# NumberMaze.net
KiCad netlist of a schematic drawn in EAGLE
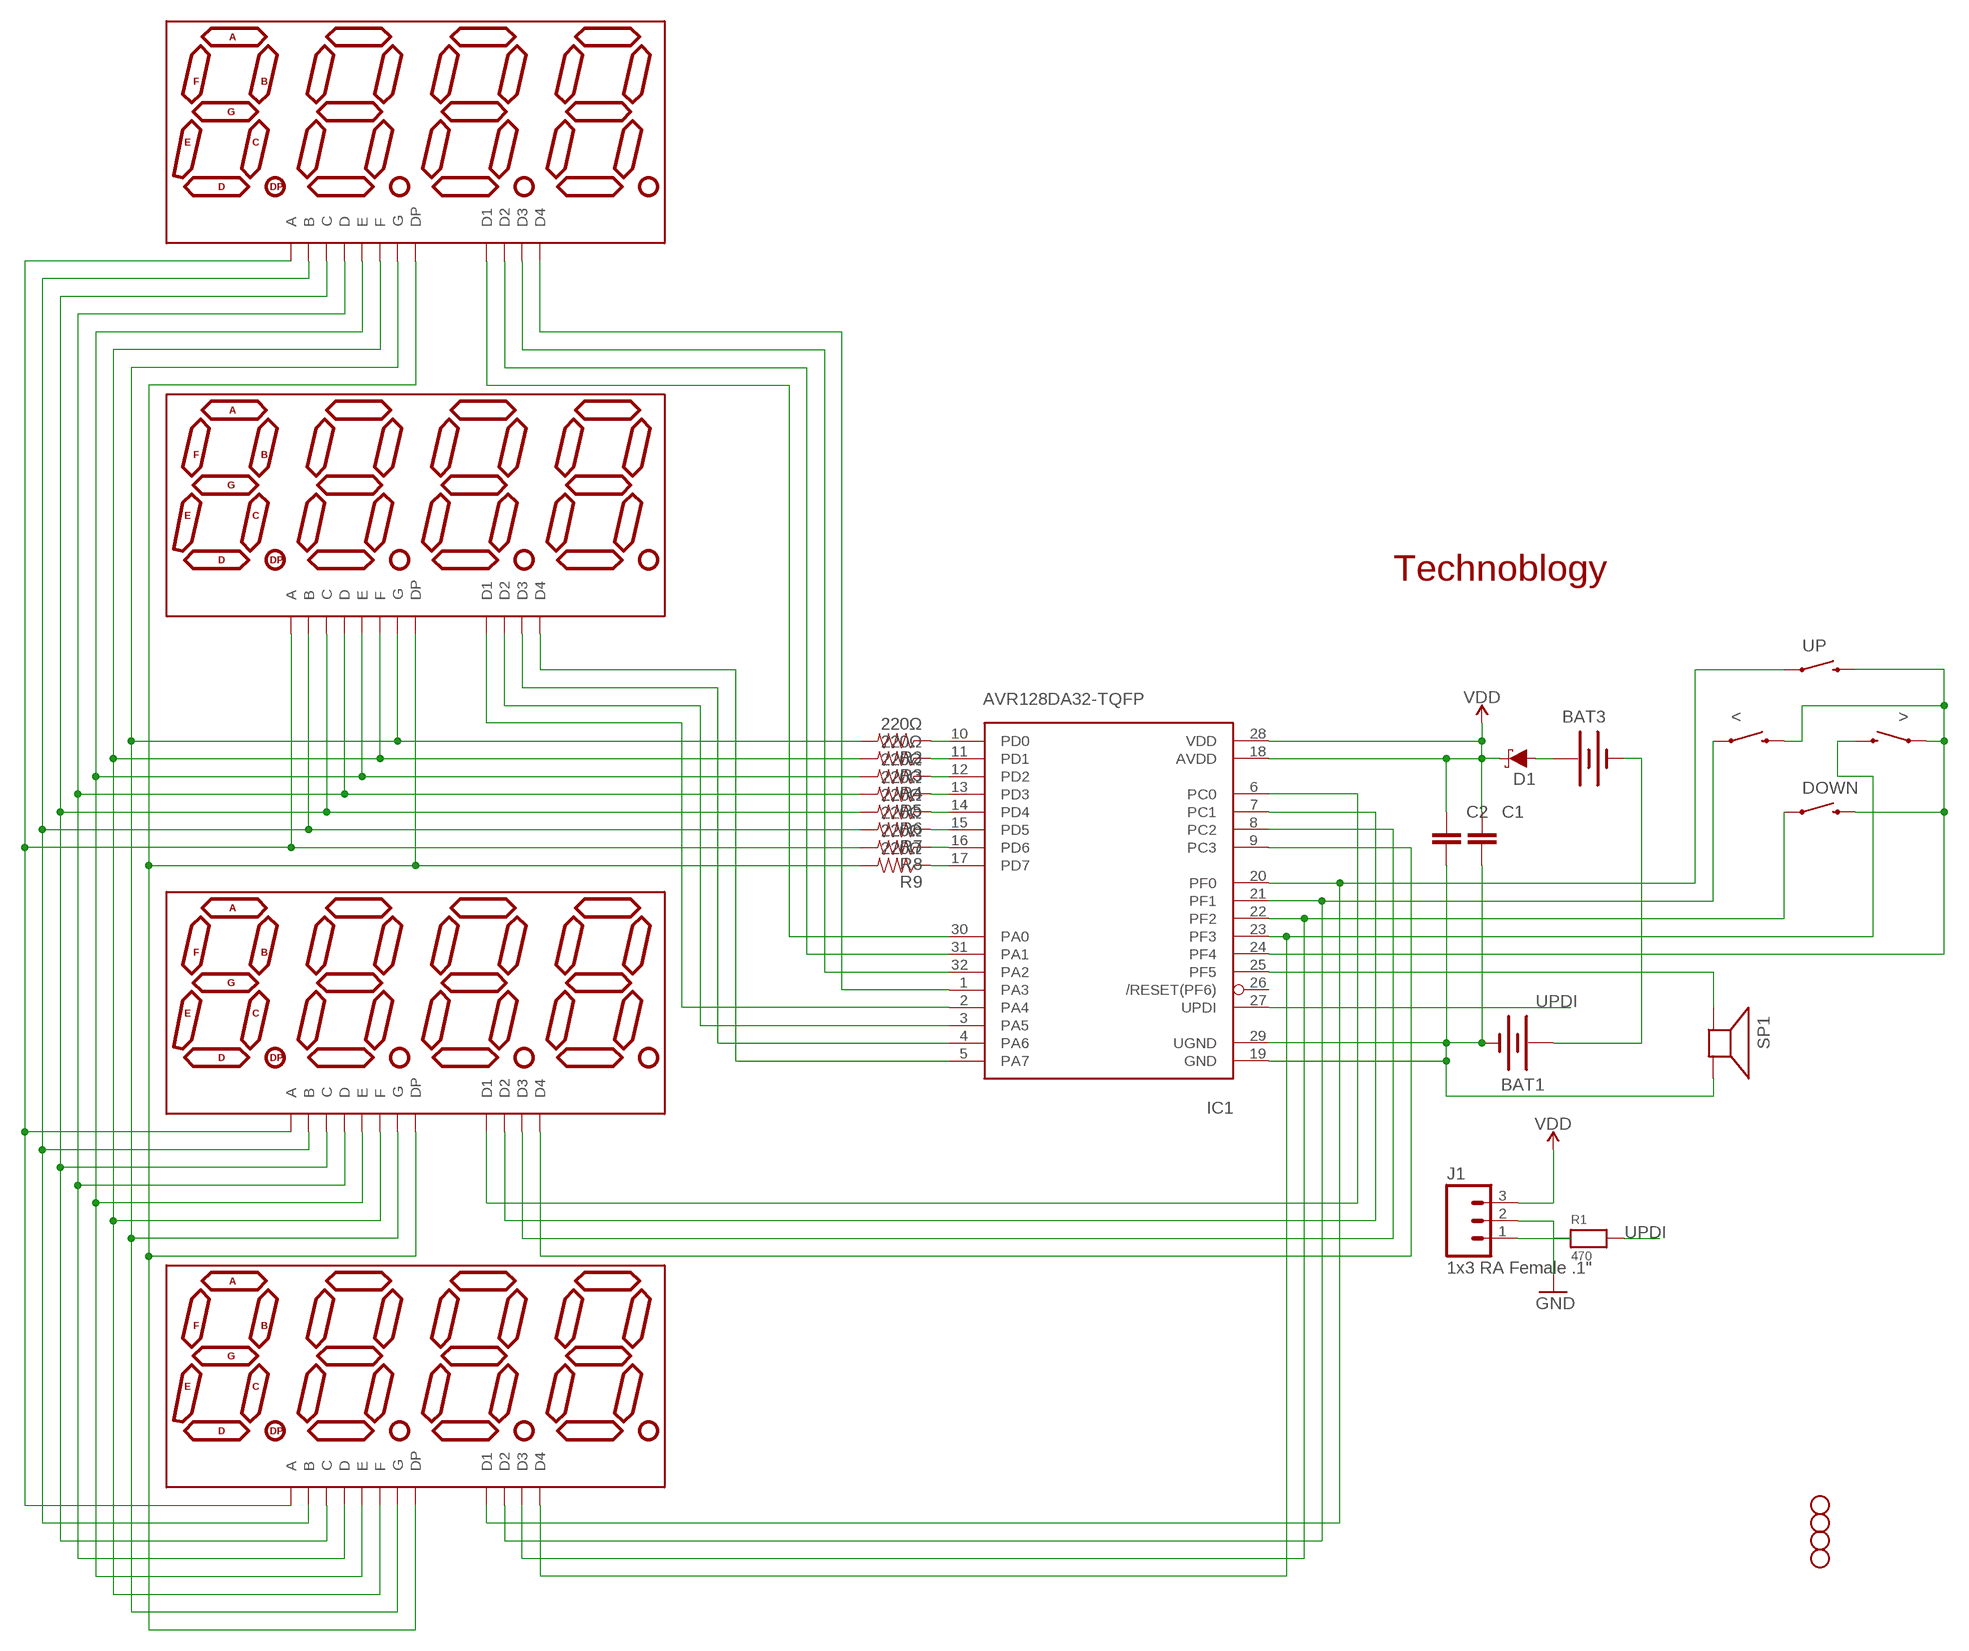
[diagram p0: schematic, sheet 1]

(export (version "E")
  (design (tool "Eeschema 10.0.6"))
  (components
    (comp (ref "<")
      (value "SWITCH-MOMENTARY-2PTH")
      (footprint "eagle-import:TACTILE-PTH")
      (libsource (lib "eagle-import") (part "SWITCH-MOMENTARY-2PTH"))
    )
    (comp (ref ">")
      (value "SWITCH-MOMENTARY-2PTH")
      (footprint "eagle-import:TACTILE-PTH")
      (libsource (lib "eagle-import") (part "SWITCH-MOMENTARY-2PTH"))
    )
    (comp (ref "BAT1")
      (value "BATTERYAA-KIT")
      (footprint "eagle-import:BATTERY-AA-KIT")
      (libsource (lib "eagle-import") (part "BATTERYAA-KIT"))
    )
    (comp (ref "BAT3")
      (value "BATTERYAA-KIT")
      (footprint "eagle-import:BATTERY-AA-KIT")
      (libsource (lib "eagle-import") (part "BATTERYAA-KIT"))
    )
    (comp (ref "C1")
      (value "100n")
      (footprint "eagle-import:0805")
      (libsource (lib "eagle-import") (part "CAP0805"))
    )
    (comp (ref "C2")
      (value "100n")
      (footprint "eagle-import:0805")
      (libsource (lib "eagle-import") (part "CAP0805"))
    )
    (comp (ref "D1")
      (value "3A/10V/280mV")
      (footprint "eagle-import:SOD-323")
      (libsource (lib "eagle-import") (part "DIODE-SCHOTTKY-BAT60A"))
    )
    (comp (ref "DISP1")
      (value "KYX-2381")
      (footprint "eagle-import:KYX-2381")
      (libsource (lib "eagle-import") (part "LD-2481-KYX-2381"))
    )
    (comp (ref "DISP2")
      (value "KYX-2381")
      (footprint "eagle-import:KYX-2381")
      (libsource (lib "eagle-import") (part "LD-2481-KYX-2381"))
    )
    (comp (ref "DISP3")
      (value "KYX-2381")
      (footprint "eagle-import:KYX-2381")
      (libsource (lib "eagle-import") (part "LD-2481-KYX-2381"))
    )
    (comp (ref "DISP4")
      (value "KYX-2381")
      (footprint "eagle-import:KYX-2381")
      (libsource (lib "eagle-import") (part "LD-2481-KYX-2381"))
    )
    (comp (ref "DOWN")
      (value "SWITCH-MOMENTARY-2PTH")
      (footprint "eagle-import:TACTILE-PTH")
      (libsource (lib "eagle-import") (part "SWITCH-MOMENTARY-2PTH"))
    )
    (comp (ref "IC1")
      (value "AVR128DA32-TQFP")
      (footprint "eagle-import:TQFP32-08")
      (libsource (lib "eagle-import") (part "AVR128DA32-TQFP"))
    )
    (comp (ref "J1")
      (value "1x3 RA Female .1\"")
      (footprint "eagle-import:1X03_SMD_RA_FEMALE")
      (libsource (lib "eagle-import") (part "M03SMD_RA_FEMALE"))
    )
    (comp (ref "JP1")
      (value "STAND-OFF")
      (footprint "eagle-import:STAND-OFF")
      (libsource (lib "eagle-import") (part "STAND-OFF"))
    )
    (comp (ref "JP2")
      (value "STAND-OFF")
      (footprint "eagle-import:STAND-OFF")
      (libsource (lib "eagle-import") (part "STAND-OFF"))
    )
    (comp (ref "JP4")
      (value "STAND-OFF")
      (footprint "eagle-import:STAND-OFF")
      (libsource (lib "eagle-import") (part "STAND-OFF"))
    )
    (comp (ref "JP5")
      (value "STAND-OFF")
      (footprint "eagle-import:STAND-OFF")
      (libsource (lib "eagle-import") (part "STAND-OFF"))
    )
    (comp (ref "R1")
      (value "470")
      (footprint "eagle-import:_0805MP")
      (libsource (lib "eagle-import") (part "RESISTOR_0805MP"))
    )
    (comp (ref "R2")
      (value "220Ω")
      (footprint "eagle-import:0805")
      (libsource (lib "eagle-import") (part "RESISTOR0805-RES"))
    )
    (comp (ref "R3")
      (value "220Ω")
      (footprint "eagle-import:0805")
      (libsource (lib "eagle-import") (part "RESISTOR0805-RES"))
    )
    (comp (ref "R4")
      (value "220Ω")
      (footprint "eagle-import:0805")
      (libsource (lib "eagle-import") (part "RESISTOR0805-RES"))
    )
    (comp (ref "R5")
      (value "220Ω")
      (footprint "eagle-import:0805")
      (libsource (lib "eagle-import") (part "RESISTOR0805-RES"))
    )
    (comp (ref "R6")
      (value "220Ω")
      (footprint "eagle-import:0805")
      (libsource (lib "eagle-import") (part "RESISTOR0805-RES"))
    )
    (comp (ref "R7")
      (value "220Ω")
      (footprint "eagle-import:0805")
      (libsource (lib "eagle-import") (part "RESISTOR0805-RES"))
    )
    (comp (ref "R8")
      (value "220Ω")
      (footprint "eagle-import:0805")
      (libsource (lib "eagle-import") (part "RESISTOR0805-RES"))
    )
    (comp (ref "R9")
      (value "220Ω")
      (footprint "eagle-import:0805")
      (libsource (lib "eagle-import") (part "RESISTOR0805-RES"))
    )
    (comp (ref "SP1")
      (value "SPEAKER/AL60P")
      (footprint "eagle-import:AL60P")
      (libsource (lib "eagle-import") (part "SPEAKER/AL60P"))
    )
    (comp (ref "UP")
      (value "SWITCH-MOMENTARY-2PTH")
      (footprint "eagle-import:TACTILE-PTH")
      (libsource (lib "eagle-import") (part "SWITCH-MOMENTARY-2PTH"))
    )
  )
  (nets
    (net (code "1") (name "/UPDI") (class "Default")
      (node (ref "IC1") (pin "27") (pinfunction "UPDI_27") (pintype "bidirectional"))
      (node (ref "R1") (pin "2") (pinfunction "2_2") (pintype "passive"))
    )
    (net (code "2") (name "GND") (class "Default")
      (node (ref "BAT1") (pin "GND@1") (pinfunction "-_GND@1") (pintype "power_in"))
      (node (ref "C1") (pin "2") (pinfunction "2_2") (pintype "passive"))
      (node (ref "C2") (pin "2") (pinfunction "2_2") (pintype "passive"))
      (node (ref "IC1") (pin "19") (pinfunction "GND_19") (pintype "bidirectional"))
      (node (ref "IC1") (pin "29") (pinfunction "UGND_29") (pintype "bidirectional"))
      (node (ref "J1") (pin "2") (pinfunction "2_2") (pintype "passive"))
      (node (ref "SP1") (pin "2") (pinfunction "-_2") (pintype "passive"))
    )
    (net (code "3") (name "Net-(<-2)") (class "Default")
      (node (ref "<") (pin "3") (pinfunction "2_3") (pintype "passive"))
      (node (ref ">") (pin "1") (pinfunction "1_1") (pintype "passive"))
      (node (ref "DOWN") (pin "3") (pinfunction "2_3") (pintype "passive"))
      (node (ref "IC1") (pin "24") (pinfunction "PF4_24") (pintype "bidirectional"))
      (node (ref "UP") (pin "3") (pinfunction "2_3") (pintype "passive"))
    )
    (net (code "4") (name "Net-(>-2)") (class "Default")
      (node (ref ">") (pin "3") (pinfunction "2_3") (pintype "passive"))
      (node (ref "DISP4") (pin "6") (pinfunction "D4_6") (pintype "bidirectional"))
      (node (ref "IC1") (pin "23") (pinfunction "PF3_23") (pintype "bidirectional"))
    )
    (net (code "5") (name "Net-(BAT1-+)") (class "Default")
      (node (ref "BAT1") (pin "PWR@1") (pinfunction "+_PWR@1") (pintype "power_in"))
      (node (ref "BAT3") (pin "GND@1") (pinfunction "-_GND@1") (pintype "power_in"))
    )
    (net (code "6") (name "Net-(BAT3-+)") (class "Default")
      (node (ref "BAT3") (pin "PWR@1") (pinfunction "+_PWR@1") (pintype "power_in"))
      (node (ref "D1") (pin "A") (pinfunction "A_A") (pintype "passive"))
    )
    (net (code "7") (name "Net-(DISP1-A)") (class "Default")
      (node (ref "DISP1") (pin "11") (pinfunction "A_11") (pintype "bidirectional"))
      (node (ref "DISP2") (pin "11") (pinfunction "A_11") (pintype "bidirectional"))
      (node (ref "DISP3") (pin "11") (pinfunction "A_11") (pintype "bidirectional"))
      (node (ref "DISP4") (pin "11") (pinfunction "A_11") (pintype "bidirectional"))
      (node (ref "R8") (pin "2") (pinfunction "2_2") (pintype "passive"))
    )
    (net (code "8") (name "Net-(DISP1-B)") (class "Default")
      (node (ref "DISP1") (pin "7") (pinfunction "B_7") (pintype "bidirectional"))
      (node (ref "DISP2") (pin "7") (pinfunction "B_7") (pintype "bidirectional"))
      (node (ref "DISP3") (pin "7") (pinfunction "B_7") (pintype "bidirectional"))
      (node (ref "DISP4") (pin "7") (pinfunction "B_7") (pintype "bidirectional"))
      (node (ref "R7") (pin "2") (pinfunction "2_2") (pintype "passive"))
    )
    (net (code "9") (name "Net-(DISP1-C)") (class "Default")
      (node (ref "DISP1") (pin "4") (pinfunction "C_4") (pintype "bidirectional"))
      (node (ref "DISP2") (pin "4") (pinfunction "C_4") (pintype "bidirectional"))
      (node (ref "DISP3") (pin "4") (pinfunction "C_4") (pintype "bidirectional"))
      (node (ref "DISP4") (pin "4") (pinfunction "C_4") (pintype "bidirectional"))
      (node (ref "R6") (pin "2") (pinfunction "2_2") (pintype "passive"))
    )
    (net (code "10") (name "Net-(DISP1-D)") (class "Default")
      (node (ref "DISP1") (pin "2") (pinfunction "D_2") (pintype "bidirectional"))
      (node (ref "DISP2") (pin "2") (pinfunction "D_2") (pintype "bidirectional"))
      (node (ref "DISP3") (pin "2") (pinfunction "D_2") (pintype "bidirectional"))
      (node (ref "DISP4") (pin "2") (pinfunction "D_2") (pintype "bidirectional"))
      (node (ref "R5") (pin "2") (pinfunction "2_2") (pintype "passive"))
    )
    (net (code "11") (name "Net-(DISP1-D1)") (class "Default")
      (node (ref "DISP1") (pin "12") (pinfunction "D1_12") (pintype "bidirectional"))
      (node (ref "IC1") (pin "30") (pinfunction "PA0_30") (pintype "bidirectional"))
    )
    (net (code "12") (name "Net-(DISP1-D2)") (class "Default")
      (node (ref "DISP1") (pin "9") (pinfunction "D2_9") (pintype "bidirectional"))
      (node (ref "IC1") (pin "31") (pinfunction "PA1_31") (pintype "bidirectional"))
    )
    (net (code "13") (name "Net-(DISP1-D3)") (class "Default")
      (node (ref "DISP1") (pin "8") (pinfunction "D3_8") (pintype "bidirectional"))
      (node (ref "IC1") (pin "32") (pinfunction "PA2_32") (pintype "bidirectional"))
    )
    (net (code "14") (name "Net-(DISP1-D4)") (class "Default")
      (node (ref "DISP1") (pin "6") (pinfunction "D4_6") (pintype "bidirectional"))
      (node (ref "IC1") (pin "1") (pinfunction "PA3_1") (pintype "bidirectional"))
    )
    (net (code "15") (name "Net-(DISP1-DP)") (class "Default")
      (node (ref "DISP1") (pin "3") (pinfunction "DP_3") (pintype "bidirectional"))
      (node (ref "DISP2") (pin "3") (pinfunction "DP_3") (pintype "bidirectional"))
      (node (ref "DISP3") (pin "3") (pinfunction "DP_3") (pintype "bidirectional"))
      (node (ref "DISP4") (pin "3") (pinfunction "DP_3") (pintype "bidirectional"))
      (node (ref "R9") (pin "2") (pinfunction "2_2") (pintype "passive"))
    )
    (net (code "16") (name "Net-(DISP1-E)") (class "Default")
      (node (ref "DISP1") (pin "1") (pinfunction "E_1") (pintype "bidirectional"))
      (node (ref "DISP2") (pin "1") (pinfunction "E_1") (pintype "bidirectional"))
      (node (ref "DISP3") (pin "1") (pinfunction "E_1") (pintype "bidirectional"))
      (node (ref "DISP4") (pin "1") (pinfunction "E_1") (pintype "bidirectional"))
      (node (ref "R4") (pin "2") (pinfunction "2_2") (pintype "passive"))
    )
    (net (code "17") (name "Net-(DISP1-F)") (class "Default")
      (node (ref "DISP1") (pin "10") (pinfunction "F_10") (pintype "bidirectional"))
      (node (ref "DISP2") (pin "10") (pinfunction "F_10") (pintype "bidirectional"))
      (node (ref "DISP3") (pin "10") (pinfunction "F_10") (pintype "bidirectional"))
      (node (ref "DISP4") (pin "10") (pinfunction "F_10") (pintype "bidirectional"))
      (node (ref "R3") (pin "2") (pinfunction "2_2") (pintype "passive"))
    )
    (net (code "18") (name "Net-(DISP1-G)") (class "Default")
      (node (ref "DISP1") (pin "5") (pinfunction "G_5") (pintype "bidirectional"))
      (node (ref "DISP2") (pin "5") (pinfunction "G_5") (pintype "bidirectional"))
      (node (ref "DISP3") (pin "5") (pinfunction "G_5") (pintype "bidirectional"))
      (node (ref "DISP4") (pin "5") (pinfunction "G_5") (pintype "bidirectional"))
      (node (ref "R2") (pin "2") (pinfunction "2_2") (pintype "passive"))
    )
    (net (code "19") (name "Net-(DISP2-D1)") (class "Default")
      (node (ref "DISP2") (pin "12") (pinfunction "D1_12") (pintype "bidirectional"))
      (node (ref "IC1") (pin "2") (pinfunction "PA4_2") (pintype "bidirectional"))
    )
    (net (code "20") (name "Net-(DISP2-D2)") (class "Default")
      (node (ref "DISP2") (pin "9") (pinfunction "D2_9") (pintype "bidirectional"))
      (node (ref "IC1") (pin "3") (pinfunction "PA5_3") (pintype "bidirectional"))
    )
    (net (code "21") (name "Net-(DISP2-D3)") (class "Default")
      (node (ref "DISP2") (pin "8") (pinfunction "D3_8") (pintype "bidirectional"))
      (node (ref "IC1") (pin "4") (pinfunction "PA6_4") (pintype "bidirectional"))
    )
    (net (code "22") (name "Net-(DISP2-D4)") (class "Default")
      (node (ref "DISP2") (pin "6") (pinfunction "D4_6") (pintype "bidirectional"))
      (node (ref "IC1") (pin "5") (pinfunction "PA7_5") (pintype "bidirectional"))
    )
    (net (code "23") (name "Net-(DISP3-D1)") (class "Default")
      (node (ref "DISP3") (pin "12") (pinfunction "D1_12") (pintype "bidirectional"))
      (node (ref "IC1") (pin "6") (pinfunction "PC0_6") (pintype "bidirectional"))
    )
    (net (code "24") (name "Net-(DISP3-D2)") (class "Default")
      (node (ref "DISP3") (pin "9") (pinfunction "D2_9") (pintype "bidirectional"))
      (node (ref "IC1") (pin "7") (pinfunction "PC1_7") (pintype "bidirectional"))
    )
    (net (code "25") (name "Net-(DISP3-D3)") (class "Default")
      (node (ref "DISP3") (pin "8") (pinfunction "D3_8") (pintype "bidirectional"))
      (node (ref "IC1") (pin "8") (pinfunction "PC2_8") (pintype "bidirectional"))
    )
    (net (code "26") (name "Net-(DISP3-D4)") (class "Default")
      (node (ref "DISP3") (pin "6") (pinfunction "D4_6") (pintype "bidirectional"))
      (node (ref "IC1") (pin "9") (pinfunction "PC3_9") (pintype "bidirectional"))
    )
    (net (code "27") (name "Net-(DISP4-D1)") (class "Default")
      (node (ref "DISP4") (pin "12") (pinfunction "D1_12") (pintype "bidirectional"))
      (node (ref "IC1") (pin "20") (pinfunction "PF0_20") (pintype "bidirectional"))
      (node (ref "UP") (pin "1") (pinfunction "1_1") (pintype "passive"))
    )
    (net (code "28") (name "Net-(DISP4-D2)") (class "Default")
      (node (ref "<") (pin "1") (pinfunction "1_1") (pintype "passive"))
      (node (ref "DISP4") (pin "9") (pinfunction "D2_9") (pintype "bidirectional"))
      (node (ref "IC1") (pin "21") (pinfunction "PF1_21") (pintype "bidirectional"))
    )
    (net (code "29") (name "Net-(DISP4-D3)") (class "Default")
      (node (ref "DISP4") (pin "8") (pinfunction "D3_8") (pintype "bidirectional"))
      (node (ref "DOWN") (pin "1") (pinfunction "1_1") (pintype "passive"))
      (node (ref "IC1") (pin "22") (pinfunction "PF2_22") (pintype "bidirectional"))
    )
    (net (code "30") (name "Net-(IC1-PD0)") (class "Default")
      (node (ref "IC1") (pin "10") (pinfunction "PD0_10") (pintype "bidirectional"))
      (node (ref "R2") (pin "1") (pinfunction "1_1") (pintype "passive"))
    )
    (net (code "31") (name "Net-(IC1-PD1)") (class "Default")
      (node (ref "IC1") (pin "11") (pinfunction "PD1_11") (pintype "bidirectional"))
      (node (ref "R3") (pin "1") (pinfunction "1_1") (pintype "passive"))
    )
    (net (code "32") (name "Net-(IC1-PD2)") (class "Default")
      (node (ref "IC1") (pin "12") (pinfunction "PD2_12") (pintype "bidirectional"))
      (node (ref "R4") (pin "1") (pinfunction "1_1") (pintype "passive"))
    )
    (net (code "33") (name "Net-(IC1-PD3)") (class "Default")
      (node (ref "IC1") (pin "13") (pinfunction "PD3_13") (pintype "bidirectional"))
      (node (ref "R5") (pin "1") (pinfunction "1_1") (pintype "passive"))
    )
    (net (code "34") (name "Net-(IC1-PD4)") (class "Default")
      (node (ref "IC1") (pin "14") (pinfunction "PD4_14") (pintype "bidirectional"))
      (node (ref "R6") (pin "1") (pinfunction "1_1") (pintype "passive"))
    )
    (net (code "35") (name "Net-(IC1-PD5)") (class "Default")
      (node (ref "IC1") (pin "15") (pinfunction "PD5_15") (pintype "bidirectional"))
      (node (ref "R7") (pin "1") (pinfunction "1_1") (pintype "passive"))
    )
    (net (code "36") (name "Net-(IC1-PD6)") (class "Default")
      (node (ref "IC1") (pin "16") (pinfunction "PD6_16") (pintype "bidirectional"))
      (node (ref "R8") (pin "1") (pinfunction "1_1") (pintype "passive"))
    )
    (net (code "37") (name "Net-(IC1-PD7)") (class "Default")
      (node (ref "IC1") (pin "17") (pinfunction "PD7_17") (pintype "bidirectional"))
      (node (ref "R9") (pin "1") (pinfunction "1_1") (pintype "passive"))
    )
    (net (code "38") (name "Net-(IC1-PF5)") (class "Default")
      (node (ref "IC1") (pin "25") (pinfunction "PF5_25") (pintype "bidirectional"))
      (node (ref "SP1") (pin "1") (pinfunction "+_1") (pintype "passive"))
    )
    (net (code "39") (name "Net-(J1-Pad1)") (class "Default")
      (node (ref "J1") (pin "1") (pinfunction "1_1") (pintype "passive"))
      (node (ref "R1") (pin "1") (pinfunction "1_1") (pintype "passive"))
    )
    (net (code "40") (name "VDD") (class "Default")
      (node (ref "C1") (pin "1") (pinfunction "1_1") (pintype "passive"))
      (node (ref "C2") (pin "1") (pinfunction "1_1") (pintype "passive"))
      (node (ref "D1") (pin "C") (pinfunction "C_C") (pintype "passive"))
      (node (ref "IC1") (pin "18") (pinfunction "AVDD_18") (pintype "bidirectional"))
      (node (ref "IC1") (pin "28") (pinfunction "VDD_28") (pintype "bidirectional"))
      (node (ref "J1") (pin "3") (pinfunction "3_3") (pintype "passive"))
    )
    (net (code "41") (name "unconnected-(IC1-{slash}RESET(PF6)-Pad26)") (class "Default")
      (node (ref "IC1") (pin "26") (pinfunction "/RESET(PF6)_26") (pintype "bidirectional"))
    )
  )
)
